# LCD16x2.net
KiCad netlist of a schematic drawn in Altium Designer
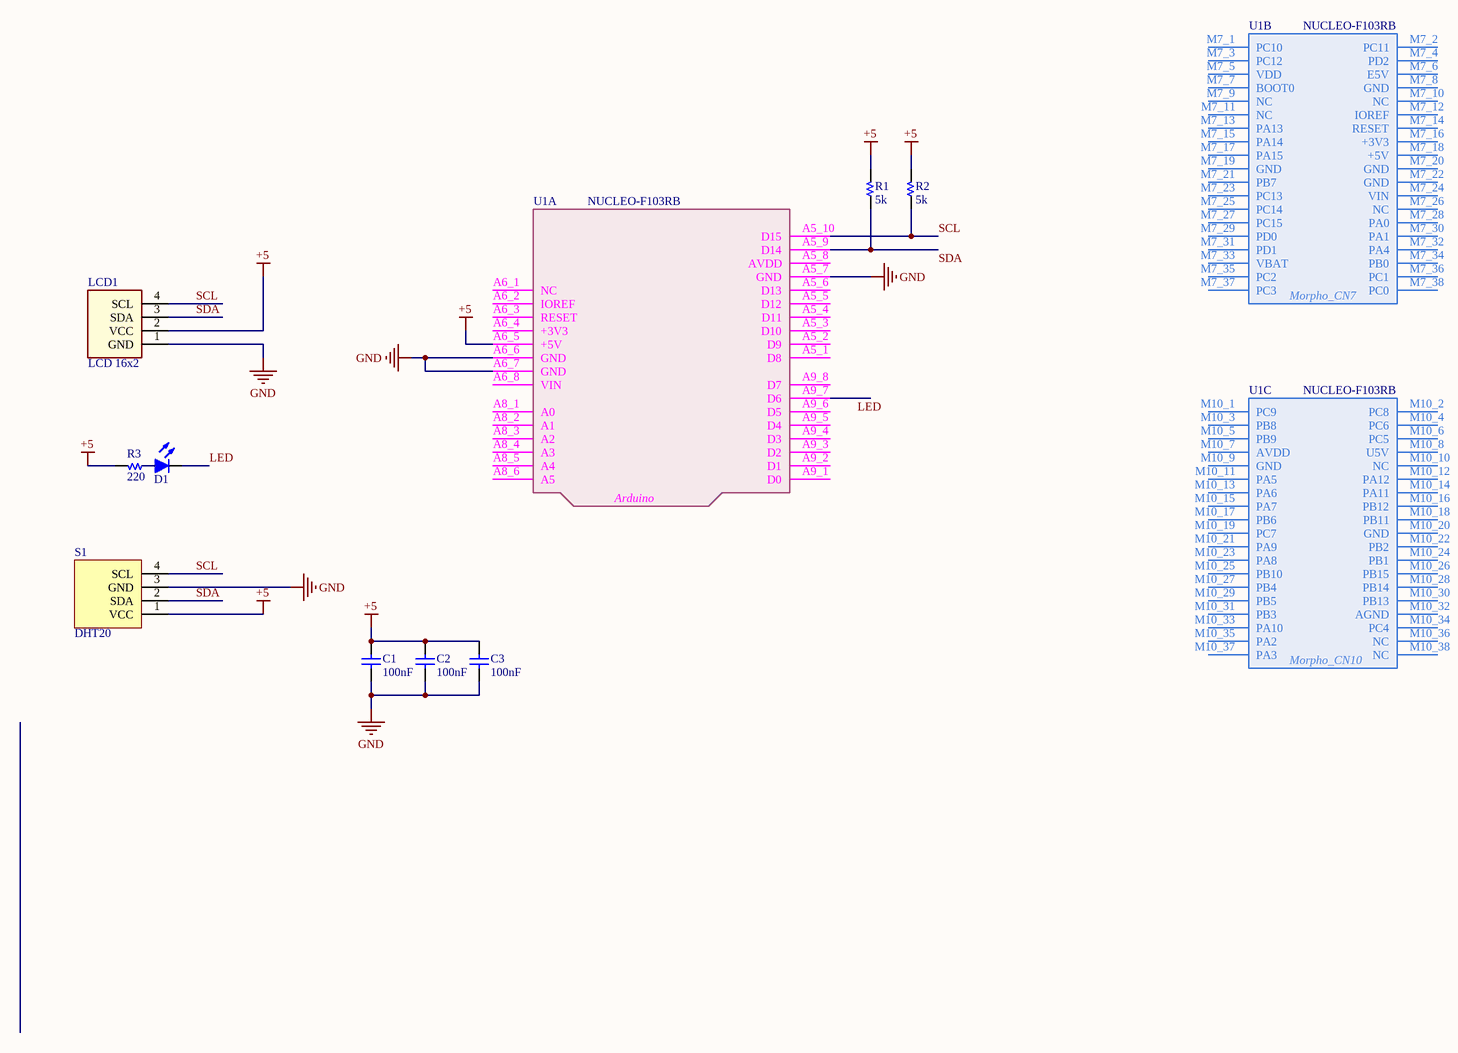
[diagram p0: LCD16x2.SchDoc]

(export (version "E")
  (design (tool "Eeschema 10.0.6"))
  (components
    (comp (ref "C1")
      (value "100nF")
      (footprint "C 0805")
      (description "Capacitor non-pol")
      (libsource (lib "chipfc_altium_libs") (part "Capacitor NP"))
    )
    (comp (ref "C2")
      (value "100nF")
      (footprint "C 0805")
      (description "Capacitor non-pol")
      (libsource (lib "chipfc_altium_libs") (part "Capacitor NP"))
    )
    (comp (ref "C3")
      (value "100nF")
      (footprint "C 0805")
      (description "Capacitor non-pol")
      (libsource (lib "chipfc_altium_libs") (part "Capacitor NP"))
    )
    (comp (ref "D1")
      (value "Led")
      (footprint "LED 3MM - red")
      (description "Typical LED")
      (libsource (lib "chipfc_altium_libs") (part "Led"))
    )
    (comp (ref "LCD1")
      (value "LCD 16x2")
      (footprint "LCD 1602A I2C")
      (description "Character LCD 16x2")
      (libsource (lib "bk2022") (part "LCD 16x2"))
    )
    (comp (ref "R1")
      (value "5k")
      (footprint "R 0805")
      (description "Resistor")
      (libsource (lib "chipfc_altium_libs") (part "Resistor"))
    )
    (comp (ref "R2")
      (value "5k")
      (footprint "R 0805")
      (description "Resistor")
      (libsource (lib "chipfc_altium_libs") (part "Resistor"))
    )
    (comp (ref "R3")
      (value "220")
      (footprint "R 0805")
      (description "Resistor")
      (libsource (lib "chipfc_altium_libs") (part "Resistor"))
    )
    (comp (ref "S1")
      (value "DHT20")
      (footprint "DTH20")
      (description "DTH20 Temperature and humidity module")
      (libsource (lib "chipfc_altium_libs") (part "DTH20"))
    )
    (comp (ref "U1")
      (value "NUCLEO-F103RB")
      (footprint "NUCLEO")
      (fields (field (name "MANUFACTURER") "STMicroelectronics"))
      (libsource (lib "nucleo") (part "NUCLEO-F103RB"))
    )
  )
  (nets
    (net (code "1") (name "+5") (class "Default")
      (node (ref "C1") (pin "1") (pinfunction "1_1") (pintype "passive"))
      (node (ref "C2") (pin "1") (pinfunction "1_1") (pintype "passive"))
      (node (ref "C3") (pin "1") (pinfunction "1_1") (pintype "passive"))
      (node (ref "LCD1") (pin "2") (pinfunction "VCC_2") (pintype "passive"))
      (node (ref "R1") (pin "2") (pinfunction "2_2") (pintype "passive"))
      (node (ref "R2") (pin "2") (pinfunction "2_2") (pintype "passive"))
      (node (ref "R3") (pin "2") (pinfunction "2_2") (pintype "passive"))
      (node (ref "S1") (pin "1") (pinfunction "VCC_1") (pintype "passive"))
      (node (ref "U1") (pin "A6_5") (pinfunction "+5V_A6_5") (pintype "passive"))
    )
    (net (code "2") (name "/LED") (class "Default")
      (node (ref "D1") (pin "2") (pinfunction "K_2") (pintype "passive"))
      (node (ref "U1") (pin "A9_7") (pinfunction "D6_A9_7") (pintype "passive"))
    )
    (net (code "3") (name "/SCL") (class "Default")
      (node (ref "LCD1") (pin "4") (pinfunction "SCL_4") (pintype "passive"))
      (node (ref "R2") (pin "1") (pinfunction "1_1") (pintype "passive"))
      (node (ref "S1") (pin "4") (pinfunction "SCL_4") (pintype "passive"))
      (node (ref "U1") (pin "A5_10") (pinfunction "D15_A5_10") (pintype "passive"))
    )
    (net (code "4") (name "/SDA") (class "Default")
      (node (ref "LCD1") (pin "3") (pinfunction "SDA_3") (pintype "passive"))
      (node (ref "R1") (pin "1") (pinfunction "1_1") (pintype "passive"))
      (node (ref "S1") (pin "2") (pinfunction "SDA_2") (pintype "passive"))
      (node (ref "U1") (pin "A5_9") (pinfunction "D14_A5_9") (pintype "passive"))
    )
    (net (code "5") (name "GND") (class "Default")
      (node (ref "C1") (pin "2") (pinfunction "2_2") (pintype "passive"))
      (node (ref "C2") (pin "2") (pinfunction "2_2") (pintype "passive"))
      (node (ref "C3") (pin "2") (pinfunction "2_2") (pintype "passive"))
      (node (ref "LCD1") (pin "1") (pinfunction "GND_1") (pintype "passive"))
      (node (ref "S1") (pin "3") (pinfunction "GND_3") (pintype "passive"))
      (node (ref "U1") (pin "A5_7") (pinfunction "GND_A5_7") (pintype "passive"))
      (node (ref "U1") (pin "A6_6") (pinfunction "GND_A6_6") (pintype "passive"))
      (node (ref "U1") (pin "A6_7") (pinfunction "GND_A6_7") (pintype "passive"))
    )
    (net (code "6") (name "Net-(D1-A)") (class "Default")
      (node (ref "D1") (pin "1") (pinfunction "A_1") (pintype "passive"))
      (node (ref "R3") (pin "1") (pinfunction "1_1") (pintype "passive"))
    )
    (net (code "7") (name "unconnected-(U1A-+3V3-PadA6_4)") (class "Default")
      (node (ref "U1") (pin "A6_4") (pinfunction "+3V3_A6_4") (pintype "passive"))
    )
    (net (code "8") (name "unconnected-(U1A-A0-PadA8_1)") (class "Default")
      (node (ref "U1") (pin "A8_1") (pinfunction "A0_A8_1") (pintype "passive"))
    )
    (net (code "9") (name "unconnected-(U1A-A1-PadA8_2)") (class "Default")
      (node (ref "U1") (pin "A8_2") (pinfunction "A1_A8_2") (pintype "passive"))
    )
    (net (code "10") (name "unconnected-(U1A-A2-PadA8_3)") (class "Default")
      (node (ref "U1") (pin "A8_3") (pinfunction "A2_A8_3") (pintype "passive"))
    )
    (net (code "11") (name "unconnected-(U1A-A3-PadA8_4)") (class "Default")
      (node (ref "U1") (pin "A8_4") (pinfunction "A3_A8_4") (pintype "passive"))
    )
    (net (code "12") (name "unconnected-(U1A-A4-PadA8_5)") (class "Default")
      (node (ref "U1") (pin "A8_5") (pinfunction "A4_A8_5") (pintype "passive"))
    )
    (net (code "13") (name "unconnected-(U1A-A5-PadA8_6)") (class "Default")
      (node (ref "U1") (pin "A8_6") (pinfunction "A5_A8_6") (pintype "passive"))
    )
    (net (code "14") (name "unconnected-(U1A-AVDD-PadA5_8)") (class "Default")
      (node (ref "U1") (pin "A5_8") (pinfunction "AVDD_A5_8") (pintype "passive"))
    )
    (net (code "15") (name "unconnected-(U1A-D0-PadA9_1)") (class "Default")
      (node (ref "U1") (pin "A9_1") (pinfunction "D0_A9_1") (pintype "passive"))
    )
    (net (code "16") (name "unconnected-(U1A-D1-PadA9_2)") (class "Default")
      (node (ref "U1") (pin "A9_2") (pinfunction "D1_A9_2") (pintype "passive"))
    )
    (net (code "17") (name "unconnected-(U1A-D2-PadA9_3)") (class "Default")
      (node (ref "U1") (pin "A9_3") (pinfunction "D2_A9_3") (pintype "passive"))
    )
    (net (code "18") (name "unconnected-(U1A-D3-PadA9_4)") (class "Default")
      (node (ref "U1") (pin "A9_4") (pinfunction "D3_A9_4") (pintype "passive"))
    )
    (net (code "19") (name "unconnected-(U1A-D4-PadA9_5)") (class "Default")
      (node (ref "U1") (pin "A9_5") (pinfunction "D4_A9_5") (pintype "passive"))
    )
    (net (code "20") (name "unconnected-(U1A-D5-PadA9_6)") (class "Default")
      (node (ref "U1") (pin "A9_6") (pinfunction "D5_A9_6") (pintype "passive"))
    )
    (net (code "21") (name "unconnected-(U1A-D7-PadA9_8)") (class "Default")
      (node (ref "U1") (pin "A9_8") (pinfunction "D7_A9_8") (pintype "passive"))
    )
    (net (code "22") (name "unconnected-(U1A-D8-PadA5_1)") (class "Default")
      (node (ref "U1") (pin "A5_1") (pinfunction "D8_A5_1") (pintype "passive"))
    )
    (net (code "23") (name "unconnected-(U1A-D9-PadA5_2)") (class "Default")
      (node (ref "U1") (pin "A5_2") (pinfunction "D9_A5_2") (pintype "passive"))
    )
    (net (code "24") (name "unconnected-(U1A-D10-PadA5_3)") (class "Default")
      (node (ref "U1") (pin "A5_3") (pinfunction "D10_A5_3") (pintype "passive"))
    )
    (net (code "25") (name "unconnected-(U1A-D11-PadA5_4)") (class "Default")
      (node (ref "U1") (pin "A5_4") (pinfunction "D11_A5_4") (pintype "passive"))
    )
    (net (code "26") (name "unconnected-(U1A-D12-PadA5_5)") (class "Default")
      (node (ref "U1") (pin "A5_5") (pinfunction "D12_A5_5") (pintype "passive"))
    )
    (net (code "27") (name "unconnected-(U1A-D13-PadA5_6)") (class "Default")
      (node (ref "U1") (pin "A5_6") (pinfunction "D13_A5_6") (pintype "passive"))
    )
    (net (code "28") (name "unconnected-(U1A-IOREF-PadA6_2)") (class "Default")
      (node (ref "U1") (pin "A6_2") (pinfunction "IOREF_A6_2") (pintype "passive"))
    )
    (net (code "29") (name "unconnected-(U1A-NC-PadA6_1)") (class "Default")
      (node (ref "U1") (pin "A6_1") (pinfunction "NC_A6_1") (pintype "passive"))
    )
    (net (code "30") (name "unconnected-(U1A-RESET-PadA6_3)") (class "Default")
      (node (ref "U1") (pin "A6_3") (pinfunction "RESET_A6_3") (pintype "passive"))
    )
    (net (code "31") (name "unconnected-(U1A-VIN-PadA6_8)") (class "Default")
      (node (ref "U1") (pin "A6_8") (pinfunction "VIN_A6_8") (pintype "passive"))
    )
    (net (code "32") (name "unconnected-(U1B-+3V3-PadM7_16)") (class "Default")
      (node (ref "U1") (pin "M7_16") (pinfunction "+3V3_M7_16") (pintype "passive"))
    )
    (net (code "33") (name "unconnected-(U1B-+5V-PadM7_18)") (class "Default")
      (node (ref "U1") (pin "M7_18") (pinfunction "+5V_M7_18") (pintype "passive"))
    )
    (net (code "34") (name "unconnected-(U1B-BOOT0-PadM7_7)") (class "Default")
      (node (ref "U1") (pin "M7_7") (pinfunction "BOOT0_M7_7") (pintype "passive"))
    )
    (net (code "35") (name "unconnected-(U1B-E5V-PadM7_6)") (class "Default")
      (node (ref "U1") (pin "M7_6") (pinfunction "E5V_M7_6") (pintype "passive"))
    )
    (net (code "36") (name "unconnected-(U1B-GND-PadM7_8)") (class "Default")
      (node (ref "U1") (pin "M7_8") (pinfunction "GND_M7_8") (pintype "passive"))
    )
    (net (code "37") (name "unconnected-(U1B-GND-PadM7_19)") (class "Default")
      (node (ref "U1") (pin "M7_19") (pinfunction "GND_M7_19") (pintype "passive"))
    )
    (net (code "38") (name "unconnected-(U1B-GND-PadM7_20)") (class "Default")
      (node (ref "U1") (pin "M7_20") (pinfunction "GND_M7_20") (pintype "passive"))
    )
    (net (code "39") (name "unconnected-(U1B-GND-PadM7_22)") (class "Default")
      (node (ref "U1") (pin "M7_22") (pinfunction "GND_M7_22") (pintype "passive"))
    )
    (net (code "40") (name "unconnected-(U1B-IOREF-PadM7_12)") (class "Default")
      (node (ref "U1") (pin "M7_12") (pinfunction "IOREF_M7_12") (pintype "passive"))
    )
    (net (code "41") (name "unconnected-(U1B-NC-PadM7_9)") (class "Default")
      (node (ref "U1") (pin "M7_9") (pinfunction "NC_M7_9") (pintype "passive"))
    )
    (net (code "42") (name "unconnected-(U1B-NC-PadM7_10)") (class "Default")
      (node (ref "U1") (pin "M7_10") (pinfunction "NC_M7_10") (pintype "passive"))
    )
    (net (code "43") (name "unconnected-(U1B-NC-PadM7_11)") (class "Default")
      (node (ref "U1") (pin "M7_11") (pinfunction "NC_M7_11") (pintype "passive"))
    )
    (net (code "44") (name "unconnected-(U1B-NC-PadM7_26)") (class "Default")
      (node (ref "U1") (pin "M7_26") (pinfunction "NC_M7_26") (pintype "passive"))
    )
    (net (code "45") (name "unconnected-(U1B-PA0-PadM7_28)") (class "Default")
      (node (ref "U1") (pin "M7_28") (pinfunction "PA0_M7_28") (pintype "passive"))
    )
    (net (code "46") (name "unconnected-(U1B-PA1-PadM7_30)") (class "Default")
      (node (ref "U1") (pin "M7_30") (pinfunction "PA1_M7_30") (pintype "passive"))
    )
    (net (code "47") (name "unconnected-(U1B-PA4-PadM7_32)") (class "Default")
      (node (ref "U1") (pin "M7_32") (pinfunction "PA4_M7_32") (pintype "passive"))
    )
    (net (code "48") (name "unconnected-(U1B-PA13-PadM7_13)") (class "Default")
      (node (ref "U1") (pin "M7_13") (pinfunction "PA13_M7_13") (pintype "passive"))
    )
    (net (code "49") (name "unconnected-(U1B-PA14-PadM7_15)") (class "Default")
      (node (ref "U1") (pin "M7_15") (pinfunction "PA14_M7_15") (pintype "passive"))
    )
    (net (code "50") (name "unconnected-(U1B-PA15-PadM7_17)") (class "Default")
      (node (ref "U1") (pin "M7_17") (pinfunction "PA15_M7_17") (pintype "passive"))
    )
    (net (code "51") (name "unconnected-(U1B-PB0-PadM7_34)") (class "Default")
      (node (ref "U1") (pin "M7_34") (pinfunction "PB0_M7_34") (pintype "passive"))
    )
    (net (code "52") (name "unconnected-(U1B-PB7-PadM7_21)") (class "Default")
      (node (ref "U1") (pin "M7_21") (pinfunction "PB7_M7_21") (pintype "passive"))
    )
    (net (code "53") (name "unconnected-(U1B-PC0-PadM7_38)") (class "Default")
      (node (ref "U1") (pin "M7_38") (pinfunction "PC0_M7_38") (pintype "passive"))
    )
    (net (code "54") (name "unconnected-(U1B-PC1-PadM7_36)") (class "Default")
      (node (ref "U1") (pin "M7_36") (pinfunction "PC1_M7_36") (pintype "passive"))
    )
    (net (code "55") (name "unconnected-(U1B-PC2-PadM7_35)") (class "Default")
      (node (ref "U1") (pin "M7_35") (pinfunction "PC2_M7_35") (pintype "passive"))
    )
    (net (code "56") (name "unconnected-(U1B-PC3-PadM7_37)") (class "Default")
      (node (ref "U1") (pin "M7_37") (pinfunction "PC3_M7_37") (pintype "passive"))
    )
    (net (code "57") (name "unconnected-(U1B-PC10-PadM7_1)") (class "Default")
      (node (ref "U1") (pin "M7_1") (pinfunction "PC10_M7_1") (pintype "passive"))
    )
    (net (code "58") (name "unconnected-(U1B-PC11-PadM7_2)") (class "Default")
      (node (ref "U1") (pin "M7_2") (pinfunction "PC11_M7_2") (pintype "passive"))
    )
    (net (code "59") (name "unconnected-(U1B-PC12-PadM7_3)") (class "Default")
      (node (ref "U1") (pin "M7_3") (pinfunction "PC12_M7_3") (pintype "passive"))
    )
    (net (code "60") (name "unconnected-(U1B-PC13-PadM7_23)") (class "Default")
      (node (ref "U1") (pin "M7_23") (pinfunction "PC13_M7_23") (pintype "passive"))
    )
    (net (code "61") (name "unconnected-(U1B-PC14-PadM7_25)") (class "Default")
      (node (ref "U1") (pin "M7_25") (pinfunction "PC14_M7_25") (pintype "passive"))
    )
    (net (code "62") (name "unconnected-(U1B-PC15-PadM7_27)") (class "Default")
      (node (ref "U1") (pin "M7_27") (pinfunction "PC15_M7_27") (pintype "passive"))
    )
    (net (code "63") (name "unconnected-(U1B-PD0-PadM7_29)") (class "Default")
      (node (ref "U1") (pin "M7_29") (pinfunction "PD0_M7_29") (pintype "passive"))
    )
    (net (code "64") (name "unconnected-(U1B-PD1-PadM7_31)") (class "Default")
      (node (ref "U1") (pin "M7_31") (pinfunction "PD1_M7_31") (pintype "passive"))
    )
    (net (code "65") (name "unconnected-(U1B-PD2-PadM7_4)") (class "Default")
      (node (ref "U1") (pin "M7_4") (pinfunction "PD2_M7_4") (pintype "passive"))
    )
    (net (code "66") (name "unconnected-(U1B-RESET-PadM7_14)") (class "Default")
      (node (ref "U1") (pin "M7_14") (pinfunction "RESET_M7_14") (pintype "passive"))
    )
    (net (code "67") (name "unconnected-(U1B-VBAT-PadM7_33)") (class "Default")
      (node (ref "U1") (pin "M7_33") (pinfunction "VBAT_M7_33") (pintype "passive"))
    )
    (net (code "68") (name "unconnected-(U1B-VDD-PadM7_5)") (class "Default")
      (node (ref "U1") (pin "M7_5") (pinfunction "VDD_M7_5") (pintype "passive"))
    )
    (net (code "69") (name "unconnected-(U1B-VIN-PadM7_24)") (class "Default")
      (node (ref "U1") (pin "M7_24") (pinfunction "VIN_M7_24") (pintype "passive"))
    )
    (net (code "70") (name "unconnected-(U1C-AGND-PadM10_32)") (class "Default")
      (node (ref "U1") (pin "M10_32") (pinfunction "AGND_M10_32") (pintype "passive"))
    )
    (net (code "71") (name "unconnected-(U1C-AVDD-PadM10_7)") (class "Default")
      (node (ref "U1") (pin "M10_7") (pinfunction "AVDD_M10_7") (pintype "passive"))
    )
    (net (code "72") (name "unconnected-(U1C-GND-PadM10_9)") (class "Default")
      (node (ref "U1") (pin "M10_9") (pinfunction "GND_M10_9") (pintype "passive"))
    )
    (net (code "73") (name "unconnected-(U1C-GND-PadM10_20)") (class "Default")
      (node (ref "U1") (pin "M10_20") (pinfunction "GND_M10_20") (pintype "passive"))
    )
    (net (code "74") (name "unconnected-(U1C-NC-PadM10_10)") (class "Default")
      (node (ref "U1") (pin "M10_10") (pinfunction "NC_M10_10") (pintype "passive"))
    )
    (net (code "75") (name "unconnected-(U1C-NC-PadM10_36)") (class "Default")
      (node (ref "U1") (pin "M10_36") (pinfunction "NC_M10_36") (pintype "passive"))
    )
    (net (code "76") (name "unconnected-(U1C-NC-PadM10_38)") (class "Default")
      (node (ref "U1") (pin "M10_38") (pinfunction "NC_M10_38") (pintype "passive"))
    )
    (net (code "77") (name "unconnected-(U1C-PA2-PadM10_35)") (class "Default")
      (node (ref "U1") (pin "M10_35") (pinfunction "PA2_M10_35") (pintype "passive"))
    )
    (net (code "78") (name "unconnected-(U1C-PA3-PadM10_37)") (class "Default")
      (node (ref "U1") (pin "M10_37") (pinfunction "PA3_M10_37") (pintype "passive"))
    )
    (net (code "79") (name "unconnected-(U1C-PA5-PadM10_11)") (class "Default")
      (node (ref "U1") (pin "M10_11") (pinfunction "PA5_M10_11") (pintype "passive"))
    )
    (net (code "80") (name "unconnected-(U1C-PA6-PadM10_13)") (class "Default")
      (node (ref "U1") (pin "M10_13") (pinfunction "PA6_M10_13") (pintype "passive"))
    )
    (net (code "81") (name "unconnected-(U1C-PA7-PadM10_15)") (class "Default")
      (node (ref "U1") (pin "M10_15") (pinfunction "PA7_M10_15") (pintype "passive"))
    )
    (net (code "82") (name "unconnected-(U1C-PA8-PadM10_23)") (class "Default")
      (node (ref "U1") (pin "M10_23") (pinfunction "PA8_M10_23") (pintype "passive"))
    )
    (net (code "83") (name "unconnected-(U1C-PA9-PadM10_21)") (class "Default")
      (node (ref "U1") (pin "M10_21") (pinfunction "PA9_M10_21") (pintype "passive"))
    )
    (net (code "84") (name "unconnected-(U1C-PA10-PadM10_33)") (class "Default")
      (node (ref "U1") (pin "M10_33") (pinfunction "PA10_M10_33") (pintype "passive"))
    )
    (net (code "85") (name "unconnected-(U1C-PA11-PadM10_14)") (class "Default")
      (node (ref "U1") (pin "M10_14") (pinfunction "PA11_M10_14") (pintype "passive"))
    )
    (net (code "86") (name "unconnected-(U1C-PA12-PadM10_12)") (class "Default")
      (node (ref "U1") (pin "M10_12") (pinfunction "PA12_M10_12") (pintype "passive"))
    )
    (net (code "87") (name "unconnected-(U1C-PB1-PadM10_24)") (class "Default")
      (node (ref "U1") (pin "M10_24") (pinfunction "PB1_M10_24") (pintype "passive"))
    )
    (net (code "88") (name "unconnected-(U1C-PB2-PadM10_22)") (class "Default")
      (node (ref "U1") (pin "M10_22") (pinfunction "PB2_M10_22") (pintype "passive"))
    )
    (net (code "89") (name "unconnected-(U1C-PB3-PadM10_31)") (class "Default")
      (node (ref "U1") (pin "M10_31") (pinfunction "PB3_M10_31") (pintype "passive"))
    )
    (net (code "90") (name "unconnected-(U1C-PB4-PadM10_27)") (class "Default")
      (node (ref "U1") (pin "M10_27") (pinfunction "PB4_M10_27") (pintype "passive"))
    )
    (net (code "91") (name "unconnected-(U1C-PB5-PadM10_29)") (class "Default")
      (node (ref "U1") (pin "M10_29") (pinfunction "PB5_M10_29") (pintype "passive"))
    )
    (net (code "92") (name "unconnected-(U1C-PB6-PadM10_17)") (class "Default")
      (node (ref "U1") (pin "M10_17") (pinfunction "PB6_M10_17") (pintype "passive"))
    )
    (net (code "93") (name "unconnected-(U1C-PB8-PadM10_3)") (class "Default")
      (node (ref "U1") (pin "M10_3") (pinfunction "PB8_M10_3") (pintype "passive"))
    )
    (net (code "94") (name "unconnected-(U1C-PB9-PadM10_5)") (class "Default")
      (node (ref "U1") (pin "M10_5") (pinfunction "PB9_M10_5") (pintype "passive"))
    )
    (net (code "95") (name "unconnected-(U1C-PB10-PadM10_25)") (class "Default")
      (node (ref "U1") (pin "M10_25") (pinfunction "PB10_M10_25") (pintype "passive"))
    )
    (net (code "96") (name "unconnected-(U1C-PB11-PadM10_18)") (class "Default")
      (node (ref "U1") (pin "M10_18") (pinfunction "PB11_M10_18") (pintype "passive"))
    )
    (net (code "97") (name "unconnected-(U1C-PB12-PadM10_16)") (class "Default")
      (node (ref "U1") (pin "M10_16") (pinfunction "PB12_M10_16") (pintype "passive"))
    )
    (net (code "98") (name "unconnected-(U1C-PB13-PadM10_30)") (class "Default")
      (node (ref "U1") (pin "M10_30") (pinfunction "PB13_M10_30") (pintype "passive"))
    )
    (net (code "99") (name "unconnected-(U1C-PB14-PadM10_28)") (class "Default")
      (node (ref "U1") (pin "M10_28") (pinfunction "PB14_M10_28") (pintype "passive"))
    )
    (net (code "100") (name "unconnected-(U1C-PB15-PadM10_26)") (class "Default")
      (node (ref "U1") (pin "M10_26") (pinfunction "PB15_M10_26") (pintype "passive"))
    )
    (net (code "101") (name "unconnected-(U1C-PC4-PadM10_34)") (class "Default")
      (node (ref "U1") (pin "M10_34") (pinfunction "PC4_M10_34") (pintype "passive"))
    )
    (net (code "102") (name "unconnected-(U1C-PC5-PadM10_6)") (class "Default")
      (node (ref "U1") (pin "M10_6") (pinfunction "PC5_M10_6") (pintype "passive"))
    )
    (net (code "103") (name "unconnected-(U1C-PC6-PadM10_4)") (class "Default")
      (node (ref "U1") (pin "M10_4") (pinfunction "PC6_M10_4") (pintype "passive"))
    )
    (net (code "104") (name "unconnected-(U1C-PC7-PadM10_19)") (class "Default")
      (node (ref "U1") (pin "M10_19") (pinfunction "PC7_M10_19") (pintype "passive"))
    )
    (net (code "105") (name "unconnected-(U1C-PC8-PadM10_2)") (class "Default")
      (node (ref "U1") (pin "M10_2") (pinfunction "PC8_M10_2") (pintype "passive"))
    )
    (net (code "106") (name "unconnected-(U1C-PC9-PadM10_1)") (class "Default")
      (node (ref "U1") (pin "M10_1") (pinfunction "PC9_M10_1") (pintype "passive"))
    )
    (net (code "107") (name "unconnected-(U1C-U5V-PadM10_8)") (class "Default")
      (node (ref "U1") (pin "M10_8") (pinfunction "U5V_M10_8") (pintype "passive"))
    )
  )
)
